# ORD_FV1.net
KiCad netlist of a schematic drawn in Altium Designer
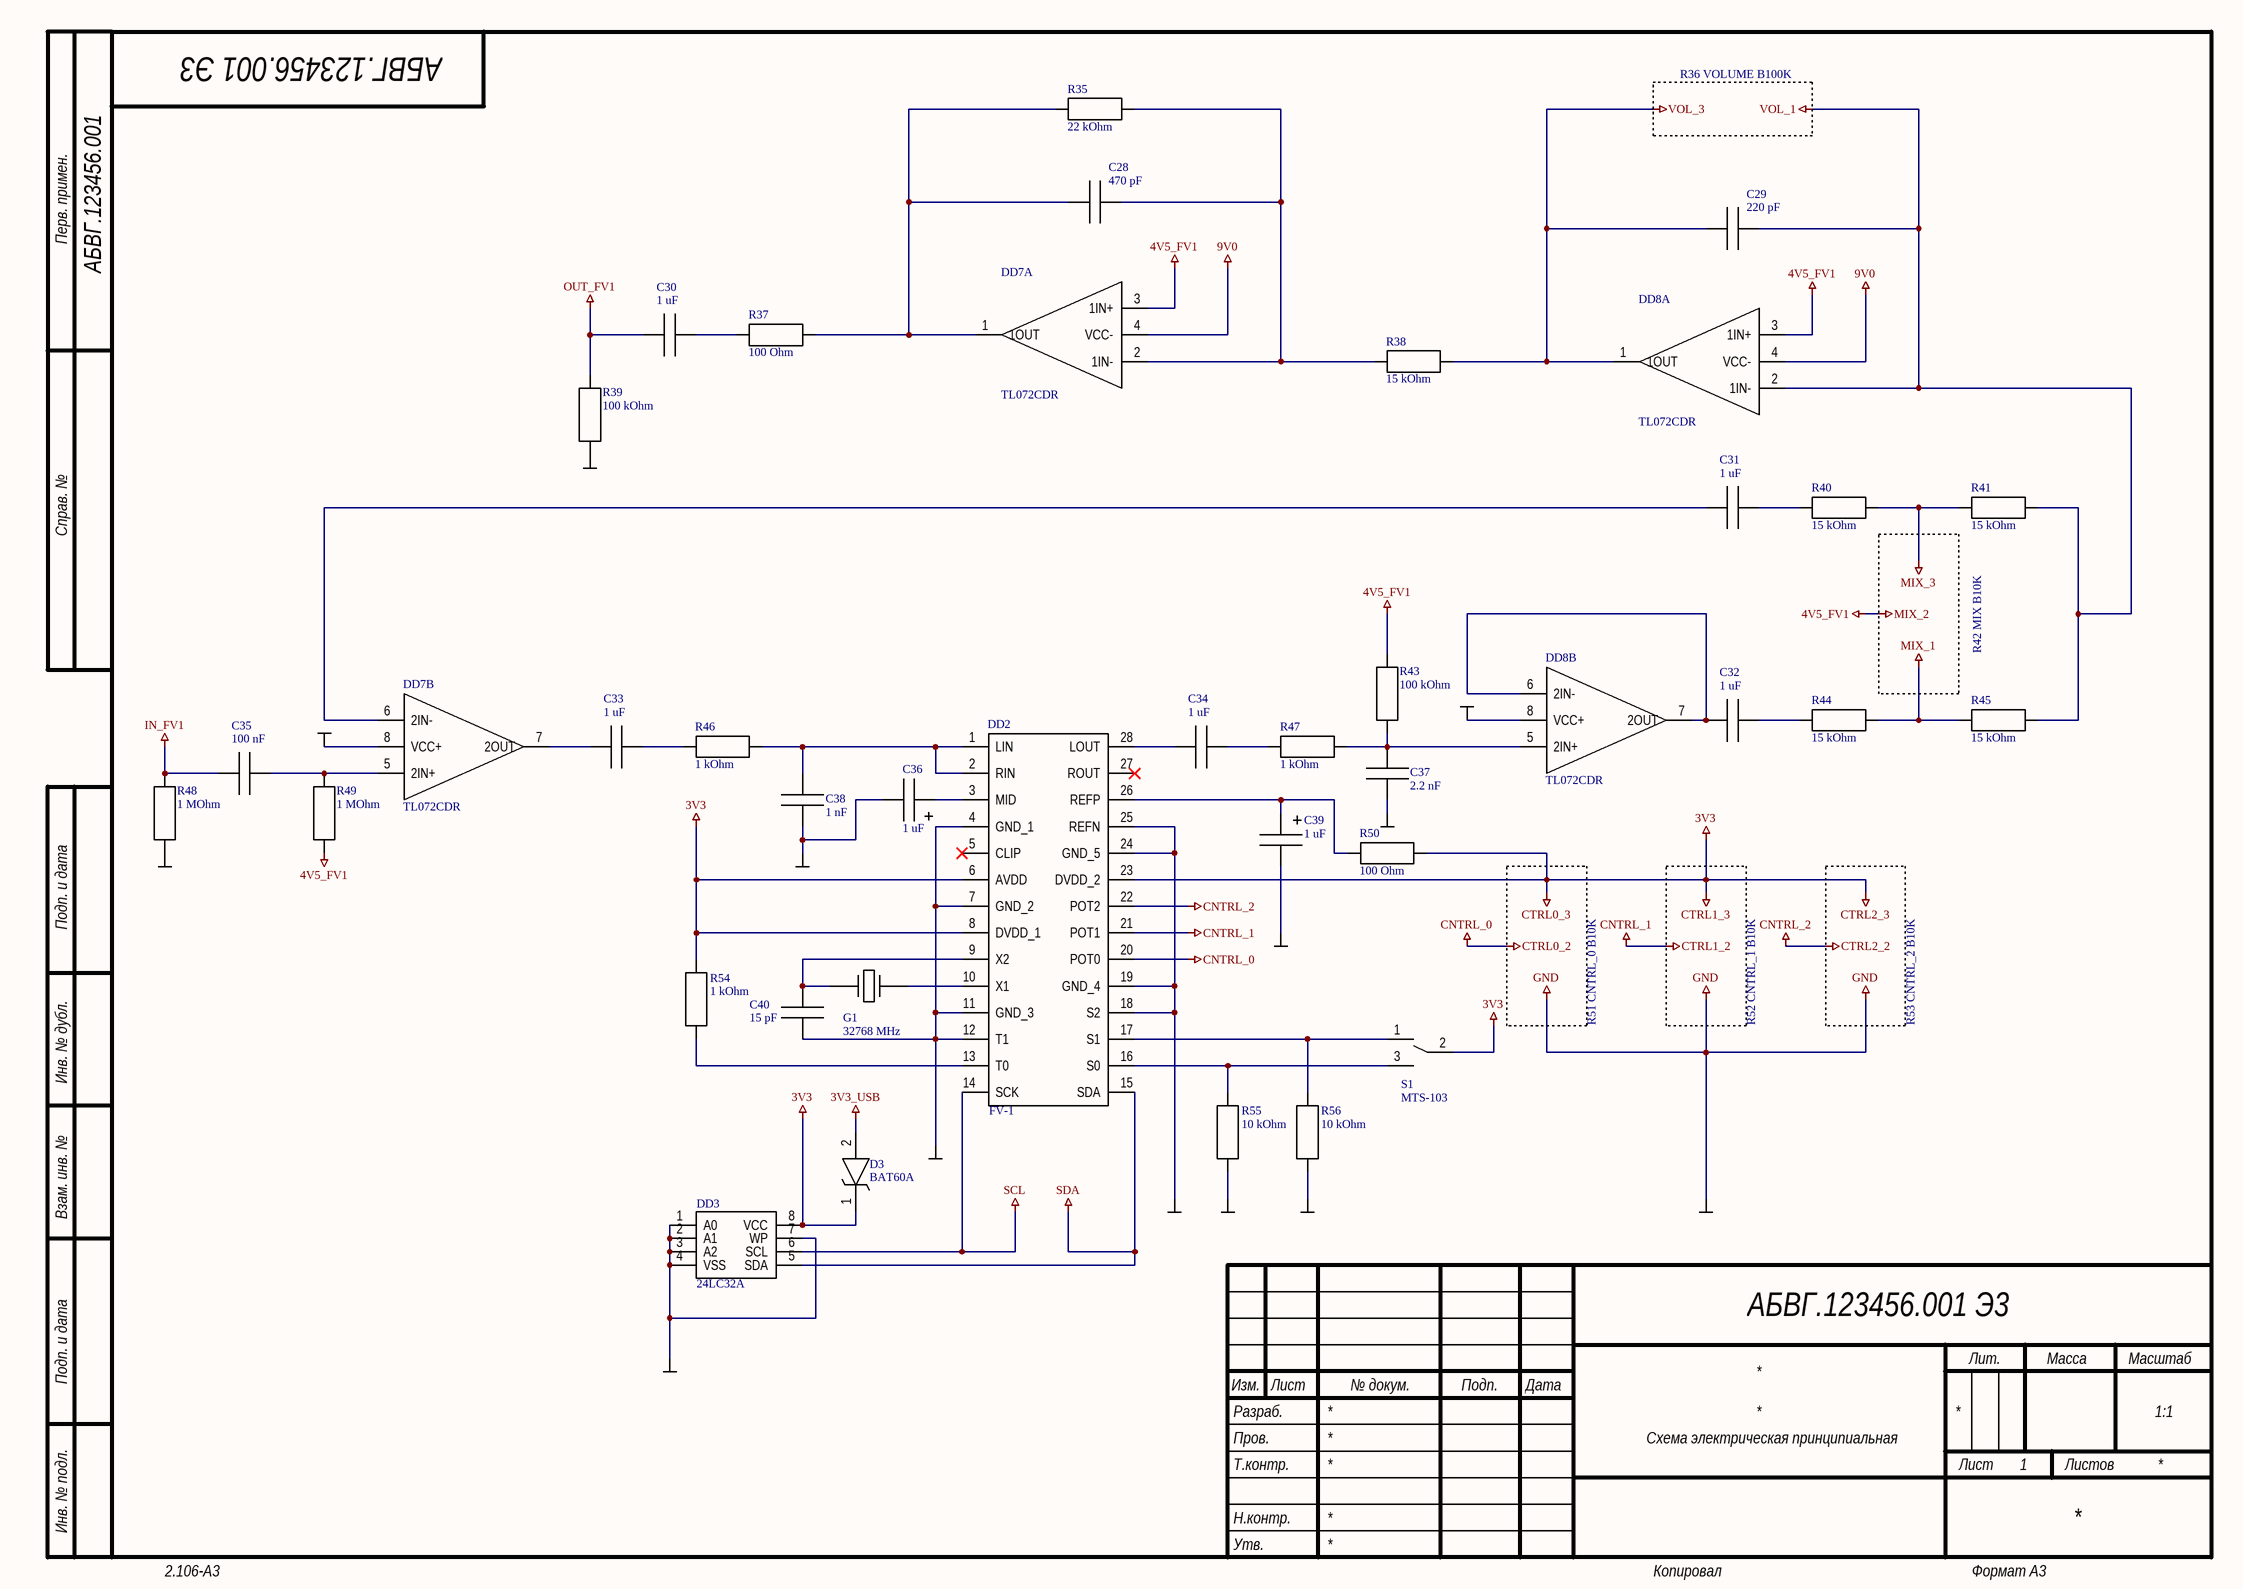
[diagram p0: ORD_FV1.SchDoc]

(export (version "E")
  (design (tool "Eeschema 10.0.6"))
  (components
    (comp (ref "C28")
      (value "470 pF")
      (footprint "C0805[2012]")
      (libsource (lib "Gost_passive_lib") (part "Capacitor"))
    )
    (comp (ref "C29")
      (value "220 pF")
      (footprint "C0805[2012]")
      (libsource (lib "Gost_passive_lib") (part "Capacitor"))
    )
    (comp (ref "C30")
      (value "1 uF")
      (footprint "C0805[2012]")
      (libsource (lib "Gost_passive_lib") (part "Capacitor"))
    )
    (comp (ref "C31")
      (value "1 uF")
      (footprint "C0805[2012]")
      (libsource (lib "Gost_passive_lib") (part "Capacitor"))
    )
    (comp (ref "C32")
      (value "1 uF")
      (footprint "C0805[2012]")
      (libsource (lib "Gost_passive_lib") (part "Capacitor"))
    )
    (comp (ref "C33")
      (value "1 uF")
      (footprint "C0805[2012]")
      (libsource (lib "Gost_passive_lib") (part "Capacitor"))
    )
    (comp (ref "C34")
      (value "1 uF")
      (footprint "C0805[2012]")
      (libsource (lib "Gost_passive_lib") (part "Capacitor"))
    )
    (comp (ref "C35")
      (value "100 nF")
      (footprint "C0805[2012]")
      (libsource (lib "Gost_passive_lib") (part "Capacitor"))
    )
    (comp (ref "C36")
      (value "1 uF")
      (footprint "C3216_CASE-A")
      (libsource (lib "Gost_passive_lib") (part "Capacitor_Pol"))
    )
    (comp (ref "C37")
      (value "2.2 nF")
      (footprint "C0805[2012]")
      (libsource (lib "Gost_passive_lib") (part "Capacitor"))
    )
    (comp (ref "C38")
      (value "1 nF")
      (footprint "C0805[2012]")
      (libsource (lib "Gost_passive_lib") (part "Capacitor"))
    )
    (comp (ref "C39")
      (value "1 uF")
      (footprint "C3216_CASE-A")
      (libsource (lib "Gost_passive_lib") (part "Capacitor_Pol"))
    )
    (comp (ref "C40")
      (value "15 pF")
      (footprint "C0805[2012]")
      (libsource (lib "Gost_passive_lib") (part "Capacitor"))
    )
    (comp (ref "D3")
      (value "BAT60A")
      (footprint "SOD323")
      (description "Diode Schottky 10V 3A Automotive 2-Pin SOD-323 T/R")
      (libsource (lib "Gost_passive_lib") (part "BAT60A"))
    )
    (comp (ref "DD2")
      (value "FV-1")
      (footprint "SOIC28")
      (description "FV-1 Reverb IC, Integrated Stereo ADC & DAC, Integrated Circuit, SOIC-28 300 MIL")
      (fields (field (name "MANUFACTURER_PART_NUMBER") "FV-1 Reverb IC"))
      (libsource (lib "Gost_active_libs") (part "FV-1"))
    )
    (comp (ref "DD3")
      (value "24LC32A")
      (footprint "DIP8_WITH_SOCKET")
      (description "32K I2C Serial EEPROM with Quarter-Array Write-Protect")
      (fields
        (field (name "MANUFACTURER_PART_NUMBER") "24LC32AF-I/P")
        (field (name "MOUSER PART NUMBER") "579-24LC32AF-I/P")
      )
      (libsource (lib "Gost_active_libs") (part "24LC32A"))
    )
    (comp (ref "DD7")
      (value "TL072CDR")
      (footprint "SO8")
      (description "TL072CDR, Dual Operational Amplifier 4 MHz -18 to 18V, 8-Pin SO")
      (fields
        (field (name "MANUFACTURER_PART_NUMBER") "LM358DT")
        (field (name "MOUSER PART NUMBER") "511-LM358DT")
      )
      (libsource (lib "Gost_active_libs") (part "TL072CDR"))
    )
    (comp (ref "DD8")
      (value "TL072CDR")
      (footprint "SO8")
      (description "TL072CDR, Dual Operational Amplifier 4 MHz -18 to 18V, 8-Pin SO")
      (fields
        (field (name "MANUFACTURER_PART_NUMBER") "LM358DT")
        (field (name "MOUSER PART NUMBER") "511-LM358DT")
      )
      (libsource (lib "Gost_active_libs") (part "TL072CDR"))
    )
    (comp (ref "G1")
      (value "32768 MHz")
      (footprint "HC-49")
      (libsource (lib "Gost_passive_lib") (part "Crystal_2pin"))
    )
    (comp (ref "R35")
      (value "22 kOhm")
      (footprint "R0805[2012]")
      (libsource (lib "Gost_passive_lib") (part "Resistor"))
    )
    (comp (ref "R37")
      (value "100 Ohm")
      (footprint "R0805[2012]")
      (libsource (lib "Gost_passive_lib") (part "Resistor"))
    )
    (comp (ref "R38")
      (value "15 kOhm")
      (footprint "R0805[2012]")
      (libsource (lib "Gost_passive_lib") (part "Resistor"))
    )
    (comp (ref "R39")
      (value "100 kOhm")
      (footprint "R0805[2012]")
      (libsource (lib "Gost_passive_lib") (part "Resistor"))
    )
    (comp (ref "R40")
      (value "15 kOhm")
      (footprint "R0805[2012]")
      (libsource (lib "Gost_passive_lib") (part "Resistor"))
    )
    (comp (ref "R41")
      (value "15 kOhm")
      (footprint "R0805[2012]")
      (libsource (lib "Gost_passive_lib") (part "Resistor"))
    )
    (comp (ref "R43")
      (value "100 kOhm")
      (footprint "R0805[2012]")
      (libsource (lib "Gost_passive_lib") (part "Resistor"))
    )
    (comp (ref "R44")
      (value "15 kOhm")
      (footprint "R0805[2012]")
      (libsource (lib "Gost_passive_lib") (part "Resistor"))
    )
    (comp (ref "R45")
      (value "15 kOhm")
      (footprint "R0805[2012]")
      (libsource (lib "Gost_passive_lib") (part "Resistor"))
    )
    (comp (ref "R46")
      (value "1 kOhm")
      (footprint "R0805[2012]")
      (libsource (lib "Gost_passive_lib") (part "Resistor"))
    )
    (comp (ref "R47")
      (value "1 kOhm")
      (footprint "R0805[2012]")
      (libsource (lib "Gost_passive_lib") (part "Resistor"))
    )
    (comp (ref "R48")
      (value "1 MOhm")
      (footprint "R0805[2012]")
      (libsource (lib "Gost_passive_lib") (part "Resistor"))
    )
    (comp (ref "R49")
      (value "1 MOhm")
      (footprint "R0805[2012]")
      (libsource (lib "Gost_passive_lib") (part "Resistor"))
    )
    (comp (ref "R50")
      (value "100 Ohm")
      (footprint "R0805[2012]")
      (libsource (lib "Gost_passive_lib") (part "Resistor"))
    )
    (comp (ref "R54")
      (value "1 kOhm")
      (footprint "R0805[2012]")
      (libsource (lib "Gost_passive_lib") (part "Resistor"))
    )
    (comp (ref "R55")
      (value "10 kOhm")
      (footprint "R0805[2012]")
      (libsource (lib "Gost_passive_lib") (part "Resistor"))
    )
    (comp (ref "R56")
      (value "10 kOhm")
      (footprint "R0805[2012]")
      (libsource (lib "Gost_passive_lib") (part "Resistor"))
    )
    (comp (ref "S1")
      (value "MTS-103")
      (footprint "MTS-103")
      (description "Switch, ON-OFF-ON")
      (libsource (lib "Gost_connectors_lib") (part "MTS-103"))
    )
  )
  (nets
    (net (code "1") (name "3V3") (class "Default")
      (node (ref "D3") (pin "1") (pinfunction "K_1") (pintype "passive"))
      (node (ref "DD2") (pin "23") (pinfunction "DVDD_2_23") (pintype "passive"))
      (node (ref "DD2") (pin "6") (pinfunction "AVDD_6") (pintype "passive"))
      (node (ref "DD2") (pin "8") (pinfunction "DVDD_1_8") (pintype "passive"))
      (node (ref "DD3") (pin "8") (pinfunction "VCC_8") (pintype "passive"))
      (node (ref "R50") (pin "1") (pinfunction "1_1") (pintype "passive"))
      (node (ref "R54") (pin "2") (pinfunction "2_2") (pintype "passive"))
      (node (ref "S1") (pin "2") (pinfunction "2_2") (pintype "passive"))
    )
    (net (code "2") (name "3V3_USB") (class "Default")
      (node (ref "D3") (pin "2") (pinfunction "A_2") (pintype "passive"))
    )
    (net (code "3") (name "4V5_FV1") (class "Default")
      (node (ref "DD7") (pin "3") (pinfunction "1IN+_3") (pintype "passive"))
      (node (ref "DD8") (pin "3") (pinfunction "1IN+_3") (pintype "passive"))
      (node (ref "R43") (pin "1") (pinfunction "1_1") (pintype "passive"))
      (node (ref "R49") (pin "1") (pinfunction "1_1") (pintype "passive"))
    )
    (net (code "4") (name "9V0") (class "Default")
      (node (ref "DD7") (pin "4") (pinfunction "VCC-_4") (pintype "power_in"))
      (node (ref "DD8") (pin "4") (pinfunction "VCC-_4") (pintype "power_in"))
    )
    (net (code "5") (name "CNTRL_0") (class "Default")
      (node (ref "DD2") (pin "20") (pinfunction "POT0_20") (pintype "passive"))
    )
    (net (code "6") (name "CNTRL_1") (class "Default")
      (node (ref "DD2") (pin "21") (pinfunction "POT1_21") (pintype "passive"))
    )
    (net (code "7") (name "CNTRL_2") (class "Default")
      (node (ref "DD2") (pin "22") (pinfunction "POT2_22") (pintype "passive"))
    )
    (net (code "8") (name "GND") (class "Default")
      (node (ref "C36") (pin "2") (pinfunction "2_2") (pintype "passive"))
      (node (ref "C37") (pin "1") (pinfunction "1_1") (pintype "passive"))
      (node (ref "C38") (pin "1") (pinfunction "1_1") (pintype "passive"))
      (node (ref "C39") (pin "2") (pinfunction "2_2") (pintype "passive"))
      (node (ref "C40") (pin "2") (pinfunction "2_2") (pintype "passive"))
      (node (ref "DD2") (pin "11") (pinfunction "GND_3_11") (pintype "passive"))
      (node (ref "DD2") (pin "12") (pinfunction "T1_12") (pintype "passive"))
      (node (ref "DD2") (pin "18") (pinfunction "S2_18") (pintype "passive"))
      (node (ref "DD2") (pin "19") (pinfunction "GND_4_19") (pintype "passive"))
      (node (ref "DD2") (pin "24") (pinfunction "GND_5_24") (pintype "passive"))
      (node (ref "DD2") (pin "25") (pinfunction "REFN_25") (pintype "passive"))
      (node (ref "DD2") (pin "4") (pinfunction "GND_1_4") (pintype "passive"))
      (node (ref "DD2") (pin "7") (pinfunction "GND_2_7") (pintype "passive"))
      (node (ref "DD3") (pin "1") (pinfunction "A0_1") (pintype "passive"))
      (node (ref "DD3") (pin "2") (pinfunction "A1_2") (pintype "passive"))
      (node (ref "DD3") (pin "3") (pinfunction "A2_3") (pintype "passive"))
      (node (ref "DD3") (pin "4") (pinfunction "VSS_4") (pintype "passive"))
      (node (ref "DD3") (pin "7") (pinfunction "WP_7") (pintype "passive"))
      (node (ref "DD7") (pin "8") (pinfunction "VCC+_8") (pintype "power_in"))
      (node (ref "DD8") (pin "8") (pinfunction "VCC+_8") (pintype "power_in"))
      (node (ref "R39") (pin "1") (pinfunction "1_1") (pintype "passive"))
      (node (ref "R48") (pin "1") (pinfunction "1_1") (pintype "passive"))
      (node (ref "R55") (pin "1") (pinfunction "1_1") (pintype "passive"))
      (node (ref "R56") (pin "1") (pinfunction "1_1") (pintype "passive"))
    )
    (net (code "9") (name "IN_FV1") (class "Default")
      (node (ref "C35") (pin "1") (pinfunction "1_1") (pintype "passive"))
      (node (ref "R48") (pin "2") (pinfunction "2_2") (pintype "passive"))
    )
    (net (code "10") (name "MIX_1") (class "Default")
      (node (ref "R44") (pin "1") (pinfunction "1_1") (pintype "passive"))
      (node (ref "R45") (pin "2") (pinfunction "2_2") (pintype "passive"))
    )
    (net (code "11") (name "MIX_3") (class "Default")
      (node (ref "R40") (pin "1") (pinfunction "1_1") (pintype "passive"))
      (node (ref "R41") (pin "2") (pinfunction "2_2") (pintype "passive"))
    )
    (net (code "12") (name "Net-(C30-Pad2)") (class "Default")
      (node (ref "C30") (pin "2") (pinfunction "2_2") (pintype "passive"))
      (node (ref "R37") (pin "2") (pinfunction "2_2") (pintype "passive"))
    )
    (net (code "13") (name "Net-(C31-Pad2)") (class "Default")
      (node (ref "C31") (pin "2") (pinfunction "2_2") (pintype "passive"))
      (node (ref "R40") (pin "2") (pinfunction "2_2") (pintype "passive"))
    )
    (net (code "14") (name "Net-(C32-Pad2)") (class "Default")
      (node (ref "C32") (pin "2") (pinfunction "2_2") (pintype "passive"))
      (node (ref "R44") (pin "2") (pinfunction "2_2") (pintype "passive"))
    )
    (net (code "15") (name "Net-(C33-Pad2)") (class "Default")
      (node (ref "C33") (pin "2") (pinfunction "2_2") (pintype "passive"))
      (node (ref "R46") (pin "2") (pinfunction "2_2") (pintype "passive"))
    )
    (net (code "16") (name "Net-(C34-Pad2)") (class "Default")
      (node (ref "C34") (pin "2") (pinfunction "2_2") (pintype "passive"))
      (node (ref "R47") (pin "2") (pinfunction "2_2") (pintype "passive"))
    )
    (net (code "17") (name "Net-(DD2-LIN)") (class "Default")
      (node (ref "C38") (pin "2") (pinfunction "2_2") (pintype "passive"))
      (node (ref "DD2") (pin "1") (pinfunction "LIN_1") (pintype "passive"))
      (node (ref "DD2") (pin "2") (pinfunction "RIN_2") (pintype "passive"))
      (node (ref "R46") (pin "1") (pinfunction "1_1") (pintype "passive"))
    )
    (net (code "18") (name "Net-(DD2-LOUT)") (class "Default")
      (node (ref "C34") (pin "1") (pinfunction "1_1") (pintype "passive"))
      (node (ref "DD2") (pin "28") (pinfunction "LOUT_28") (pintype "passive"))
    )
    (net (code "19") (name "Net-(DD2-MID)") (class "Default")
      (node (ref "C36") (pin "1") (pinfunction "1_1") (pintype "passive"))
      (node (ref "DD2") (pin "3") (pinfunction "MID_3") (pintype "passive"))
    )
    (net (code "20") (name "Net-(DD2-REFP)") (class "Default")
      (node (ref "C39") (pin "1") (pinfunction "1_1") (pintype "passive"))
      (node (ref "DD2") (pin "26") (pinfunction "REFP_26") (pintype "passive"))
      (node (ref "R50") (pin "2") (pinfunction "2_2") (pintype "passive"))
    )
    (net (code "21") (name "Net-(DD2-S0)") (class "Default")
      (node (ref "DD2") (pin "16") (pinfunction "S0_16") (pintype "passive"))
      (node (ref "R55") (pin "2") (pinfunction "2_2") (pintype "passive"))
      (node (ref "S1") (pin "3") (pinfunction "3_3") (pintype "passive"))
    )
    (net (code "22") (name "Net-(DD2-S1)") (class "Default")
      (node (ref "DD2") (pin "17") (pinfunction "S1_17") (pintype "passive"))
      (node (ref "R56") (pin "2") (pinfunction "2_2") (pintype "passive"))
      (node (ref "S1") (pin "1") (pinfunction "1_1") (pintype "passive"))
    )
    (net (code "23") (name "Net-(DD2-T0)") (class "Default")
      (node (ref "DD2") (pin "13") (pinfunction "T0_13") (pintype "passive"))
      (node (ref "R54") (pin "1") (pinfunction "1_1") (pintype "passive"))
    )
    (net (code "24") (name "Net-(DD2-X1)") (class "Default")
      (node (ref "DD2") (pin "10") (pinfunction "X1_10") (pintype "passive"))
      (node (ref "G1") (pin "2") (pinfunction "2_2") (pintype "passive"))
    )
    (net (code "25") (name "Net-(DD2-X2)") (class "Default")
      (node (ref "C40") (pin "1") (pinfunction "1_1") (pintype "passive"))
      (node (ref "DD2") (pin "9") (pinfunction "X2_9") (pintype "passive"))
      (node (ref "G1") (pin "1") (pinfunction "1_1") (pintype "passive"))
    )
    (net (code "26") (name "Net-(DD7A-1IN-)") (class "Default")
      (node (ref "C28") (pin "2") (pinfunction "2_2") (pintype "passive"))
      (node (ref "DD7") (pin "2") (pinfunction "1IN-_2") (pintype "passive"))
      (node (ref "R35") (pin "1") (pinfunction "1_1") (pintype "passive"))
      (node (ref "R38") (pin "2") (pinfunction "2_2") (pintype "passive"))
    )
    (net (code "27") (name "Net-(DD7A-1OUT)") (class "Default")
      (node (ref "C28") (pin "1") (pinfunction "1_1") (pintype "passive"))
      (node (ref "DD7") (pin "1") (pinfunction "1OUT_1") (pintype "passive"))
      (node (ref "R35") (pin "2") (pinfunction "2_2") (pintype "passive"))
      (node (ref "R37") (pin "1") (pinfunction "1_1") (pintype "passive"))
    )
    (net (code "28") (name "Net-(DD7B-2IN+)") (class "Default")
      (node (ref "C35") (pin "2") (pinfunction "2_2") (pintype "passive"))
      (node (ref "DD7") (pin "5") (pinfunction "2IN+_5") (pintype "passive"))
      (node (ref "R49") (pin "2") (pinfunction "2_2") (pintype "passive"))
    )
    (net (code "29") (name "Net-(DD7B-2IN-)") (class "Default")
      (node (ref "C31") (pin "1") (pinfunction "1_1") (pintype "passive"))
      (node (ref "DD7") (pin "6") (pinfunction "2IN-_6") (pintype "passive"))
    )
    (net (code "30") (name "Net-(DD7B-2OUT)") (class "Default")
      (node (ref "C33") (pin "1") (pinfunction "1_1") (pintype "passive"))
      (node (ref "DD7") (pin "7") (pinfunction "2OUT_7") (pintype "passive"))
    )
    (net (code "31") (name "Net-(DD8B-2IN+)") (class "Default")
      (node (ref "C37") (pin "2") (pinfunction "2_2") (pintype "passive"))
      (node (ref "DD8") (pin "5") (pinfunction "2IN+_5") (pintype "passive"))
      (node (ref "R43") (pin "2") (pinfunction "2_2") (pintype "passive"))
      (node (ref "R47") (pin "1") (pinfunction "1_1") (pintype "passive"))
    )
    (net (code "32") (name "Net-(DD8B-2IN-)") (class "Default")
      (node (ref "C32") (pin "1") (pinfunction "1_1") (pintype "passive"))
      (node (ref "DD8") (pin "6") (pinfunction "2IN-_6") (pintype "passive"))
      (node (ref "DD8") (pin "7") (pinfunction "2OUT_7") (pintype "passive"))
    )
    (net (code "33") (name "OUT_FV1") (class "Default")
      (node (ref "C30") (pin "1") (pinfunction "1_1") (pintype "passive"))
      (node (ref "R39") (pin "2") (pinfunction "2_2") (pintype "passive"))
    )
    (net (code "34") (name "SCL") (class "Default")
      (node (ref "DD2") (pin "14") (pinfunction "SCK_14") (pintype "passive"))
      (node (ref "DD3") (pin "6") (pinfunction "SCL_6") (pintype "passive"))
    )
    (net (code "35") (name "SDA") (class "Default")
      (node (ref "DD2") (pin "15") (pinfunction "SDA_15") (pintype "passive"))
      (node (ref "DD3") (pin "5") (pinfunction "SDA_5") (pintype "passive"))
    )
    (net (code "36") (name "VOL_1") (class "Default")
      (node (ref "C29") (pin "2") (pinfunction "2_2") (pintype "passive"))
      (node (ref "DD8") (pin "2") (pinfunction "1IN-_2") (pintype "passive"))
      (node (ref "R41") (pin "1") (pinfunction "1_1") (pintype "passive"))
      (node (ref "R45") (pin "1") (pinfunction "1_1") (pintype "passive"))
    )
    (net (code "37") (name "VOL_3") (class "Default")
      (node (ref "C29") (pin "1") (pinfunction "1_1") (pintype "passive"))
      (node (ref "DD8") (pin "1") (pinfunction "1OUT_1") (pintype "passive"))
      (node (ref "R38") (pin "1") (pinfunction "1_1") (pintype "passive"))
    )
    (net (code "38") (name "unconnected-(DD2-CLIP-Pad5)") (class "Default")
      (node (ref "DD2") (pin "5") (pinfunction "CLIP_5") (pintype "passive+no_connect"))
    )
    (net (code "39") (name "unconnected-(DD2-ROUT-Pad27)") (class "Default")
      (node (ref "DD2") (pin "27") (pinfunction "ROUT_27") (pintype "passive+no_connect"))
    )
  )
)
